# SX1278.net
KiCad netlist of a schematic drawn in Altium Designer
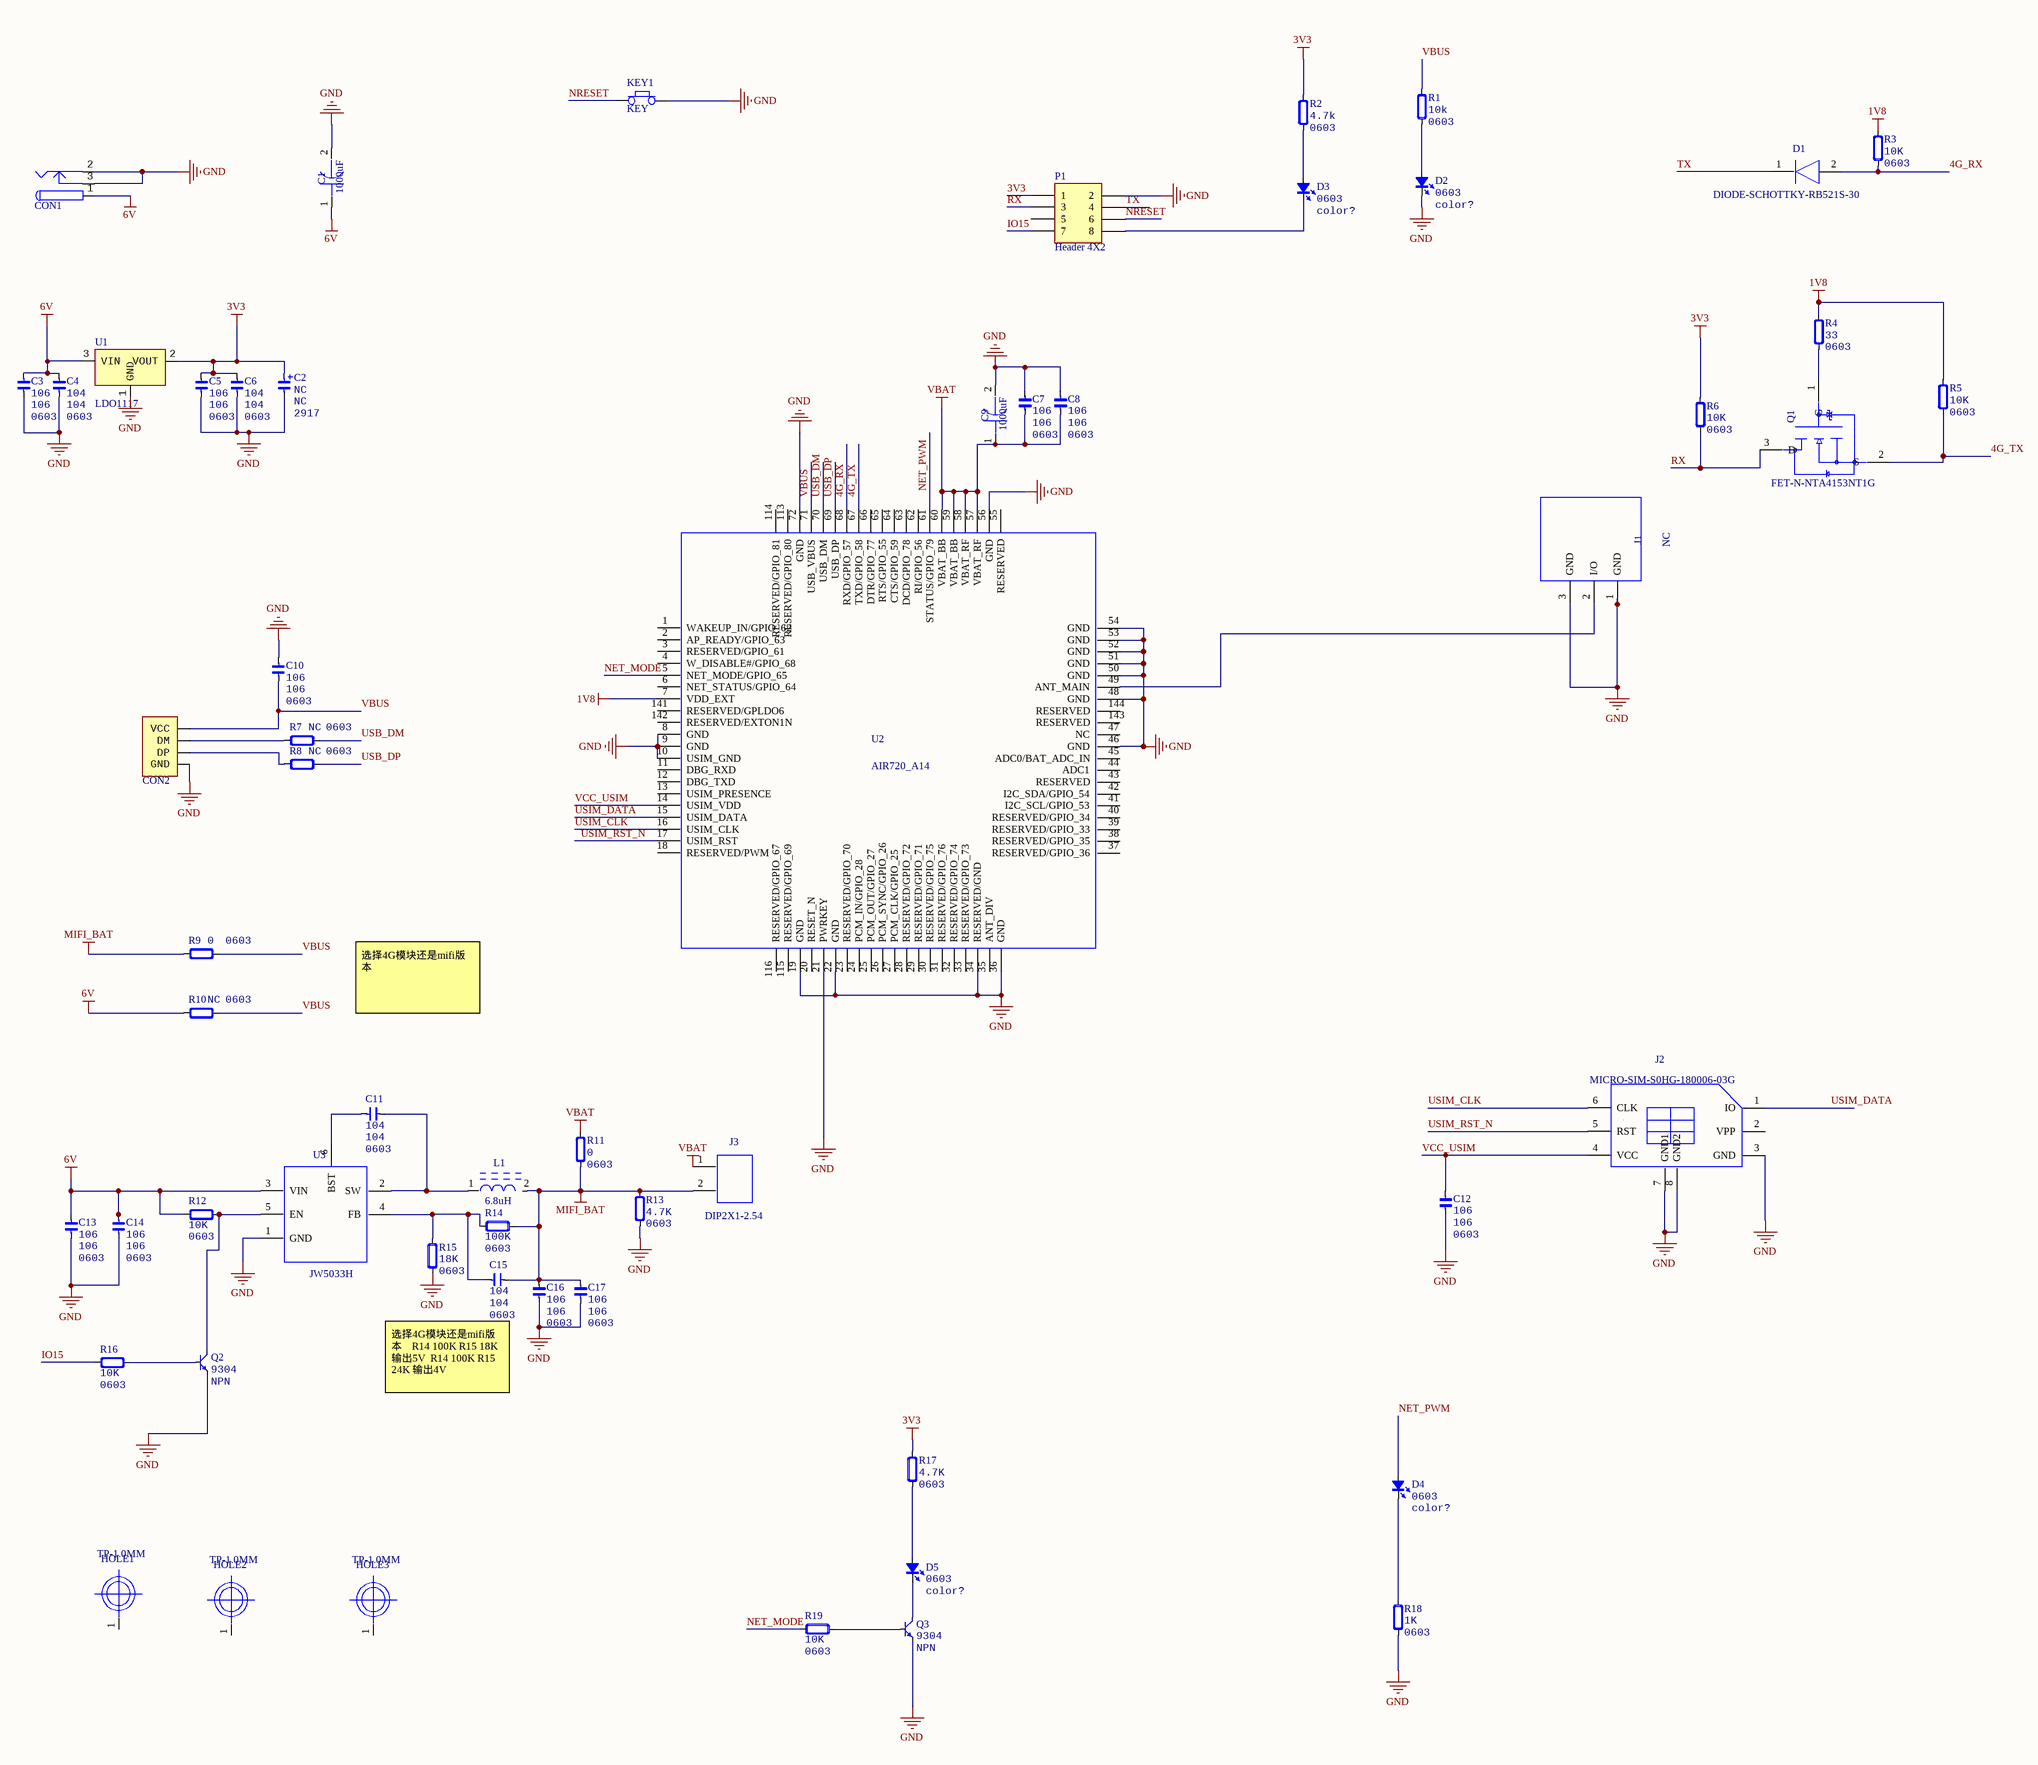
[diagram p0: SX1278.SchDoc]

(export (version "E")
  (design (tool "Eeschema 10.0.6"))
  (components
    (comp (ref "C1")
      (value "1000uF")
      (footprint "CAP-AL-1000UF-10X12")
      (description "贴片电解电容,1000uF/10V")
      (fields (field (name "Comment") "CAP-AL-1000UF-8X10.5"))
      (libsource (lib "4GMODULE") (part "CAP-AL-1000UF-8X10.5"))
    )
    (comp (ref "C2")
      (value "NC")
      (footprint "PCB_PassiveCap:CAP_TAN_D2917")
      (description "Capacitor Tantalum")
      (fields (field (name "ALTIUM_VALUE") "NC") (field (name "TYPE") "2917"))
      (libsource (lib "SCH_Passive") (part "Cap_Tan_2917"))
    )
    (comp (ref "C3")
      (value "106")
      (footprint "PCB_PassiveCap:CAP_0603")
      (description "Capacitor")
      (fields (field (name "ALTIUM_VALUE") "106") (field (name "TYPE") "0603"))
      (libsource (lib "SCH_Passive") (part "Cap_0603"))
    )
    (comp (ref "C4")
      (value "104")
      (footprint "PCB_PassiveCap:CAP_0603")
      (description "Capacitor")
      (fields (field (name "ALTIUM_VALUE") "104") (field (name "TYPE") "0603"))
      (libsource (lib "SCH_Passive") (part "Cap_0603"))
    )
    (comp (ref "C5")
      (value "106")
      (footprint "PCB_PassiveCap:CAP_0603")
      (description "Capacitor")
      (fields (field (name "ALTIUM_VALUE") "106") (field (name "TYPE") "0603"))
      (libsource (lib "SCH_Passive") (part "Cap_0603"))
    )
    (comp (ref "C6")
      (value "104")
      (footprint "PCB_PassiveCap:CAP_0603")
      (description "Capacitor")
      (fields (field (name "ALTIUM_VALUE") "104") (field (name "TYPE") "0603"))
      (libsource (lib "SCH_Passive") (part "Cap_0603"))
    )
    (comp (ref "C7")
      (value "106")
      (footprint "PCB_PassiveCap:CAP_0603")
      (description "Capacitor")
      (fields (field (name "ALTIUM_VALUE") "106") (field (name "TYPE") "0603"))
      (libsource (lib "SCH_Passive") (part "Cap_0603"))
    )
    (comp (ref "C8")
      (value "106")
      (footprint "PCB_PassiveCap:CAP_0603")
      (description "Capacitor")
      (fields (field (name "ALTIUM_VALUE") "106") (field (name "TYPE") "0603"))
      (libsource (lib "SCH_Passive") (part "Cap_0603"))
    )
    (comp (ref "C9")
      (value "1000uF")
      (footprint "CAP-AL-1000UF-10X12")
      (description "贴片电解电容,1000uF/10V")
      (fields (field (name "Comment") "CAP-AL-1000UF-8X10.5"))
      (libsource (lib "4GMODULE") (part "CAP-AL-1000UF-8X10.5"))
    )
    (comp (ref "C10")
      (value "106")
      (footprint "PCB_PassiveCap:CAP_0603")
      (description "Capacitor")
      (fields (field (name "ALTIUM_VALUE") "106") (field (name "TYPE") "0603"))
      (libsource (lib "") (part "Cap_0603_3"))
    )
    (comp (ref "C11")
      (value "104")
      (footprint "PCB_PassiveCap:CAP_0603")
      (description "Capacitor")
      (fields (field (name "ALTIUM_VALUE") "104") (field (name "TYPE") "0603"))
      (libsource (lib "") (part "Cap_0603_2"))
    )
    (comp (ref "C12")
      (value "106")
      (footprint "PCB_PassiveCap:CAP_0603")
      (description "Capacitor")
      (fields (field (name "ALTIUM_VALUE") "106") (field (name "TYPE") "0603"))
      (libsource (lib "SCH_Passive") (part "Cap_0603"))
    )
    (comp (ref "C13")
      (value "106")
      (footprint "PCB_PassiveCap:CAP_0603")
      (description "Capacitor")
      (fields (field (name "ALTIUM_VALUE") "106") (field (name "TYPE") "0603"))
      (libsource (lib "SCH_Passive") (part "Cap_0603"))
    )
    (comp (ref "C14")
      (value "106")
      (footprint "PCB_PassiveCap:CAP_0603")
      (description "Capacitor")
      (fields (field (name "ALTIUM_VALUE") "106") (field (name "TYPE") "0603"))
      (libsource (lib "SCH_Passive") (part "Cap_0603"))
    )
    (comp (ref "C15")
      (value "104")
      (footprint "PCB_PassiveCap:CAP_0603")
      (description "Capacitor")
      (fields (field (name "ALTIUM_VALUE") "104") (field (name "TYPE") "0603"))
      (libsource (lib "") (part "Cap_0603_1"))
    )
    (comp (ref "C16")
      (value "106")
      (footprint "PCB_PassiveCap:CAP_0603")
      (description "Capacitor")
      (fields (field (name "ALTIUM_VALUE") "106") (field (name "TYPE") "0603"))
      (libsource (lib "SCH_Passive") (part "Cap_0603"))
    )
    (comp (ref "C17")
      (value "106")
      (footprint "PCB_PassiveCap:CAP_0603")
      (description "Capacitor")
      (fields (field (name "ALTIUM_VALUE") "106") (field (name "TYPE") "0603"))
      (libsource (lib "SCH_Passive") (part "Cap_0603"))
    )
    (comp (ref "CON1")
      (value "PowerJack_2.5")
      (footprint "DC003A")
      (description "DC Power Jack")
      (libsource (lib "SCH_Connector") (part "PowerJack_2.5"))
    )
    (comp (ref "CON2")
      (value "USB_TypeA")
      (footprint "PCB_USB:USB_TypeA")
      (description "USB")
      (libsource (lib "SCH_USB") (part "USB_TypeA"))
    )
    (comp (ref "D1")
      (value "DIODE-SCHOTTKY-RB521S-30")
      (footprint "SOD523(RB521S)")
      (description "Schottky Diode;30V;200mA/0.6V;SOD-523;0.7mm;ROHS")
      (libsource (lib "4GMODULE") (part "DIODE-SCHOTTKY-RB521S-30"))
    )
    (comp (ref "D2")
      (value "color?")
      (footprint "PCB_ActiveLED:LED_0603_GREEN")
      (description "LED")
      (fields (field (name "TYPE") "0603"))
      (libsource (lib "SCH_Active") (part "LED_0603"))
    )
    (comp (ref "D3")
      (value "color?")
      (footprint "PCB_ActiveLED:LED_0603_GREEN")
      (description "LED")
      (fields (field (name "TYPE") "0603"))
      (libsource (lib "SCH_Active") (part "LED_0603"))
    )
    (comp (ref "D4")
      (value "color?")
      (footprint "PCB_ActiveLED:LED_0603_GREEN")
      (description "LED")
      (fields (field (name "TYPE") "0603"))
      (libsource (lib "SCH_Active") (part "LED_0603"))
    )
    (comp (ref "D5")
      (value "color?")
      (footprint "PCB_ActiveLED:LED_0603_GREEN")
      (description "LED")
      (fields (field (name "TYPE") "0603"))
      (libsource (lib "SCH_Active") (part "LED_0603"))
    )
    (comp (ref "HOLE1")
      (value "TP-1.0MM")
      (footprint "TP-1MM")
      (description "TP-1mm")
      (libsource (lib "4GMODULE") (part "TP-1.0MM"))
    )
    (comp (ref "HOLE2")
      (value "TP-1.0MM")
      (footprint "TP-1MM")
      (description "TP-1mm")
      (libsource (lib "4GMODULE") (part "TP-1.0MM"))
    )
    (comp (ref "HOLE3")
      (value "TP-1.0MM")
      (footprint "TP-1MM")
      (description "TP-1mm")
      (libsource (lib "4GMODULE") (part "TP-1.0MM"))
    )
    (comp (ref "J1")
      (value "NC")
      (footprint "RF-ANT-HJ")
      (description "RF CONNECTOR;3*3*1.25mm;ROHS")
      (fields (field (name "PART NUMBER") "1120333002051"))
      (libsource (lib "4GMODULE") (part "RF-ANT-SOCKET-U.FL-R-SMT"))
    )
    (comp (ref "J2")
      (value "MICRO-SIM-S0HG-180006-03G")
      (footprint "S0HG-180006-03G")
      (description "1.8H掀盖 Micro SIM卡座;16.3*14.66*1.8mm")
      (libsource (lib "4GMODULE") (part "MICRO-SIM-S0HG-180006-03G"))
    )
    (comp (ref "J3")
      (value "DIP2X1-2.54")
      (footprint "DIP2X1-2.54")
      (libsource (lib "4GMODULE") (part "DIP2X1-2.54"))
    )
    (comp (ref "KEY1") (value "KEY") (footprint "key_4") (libsource (lib "HEXCAL_SCH_LIB") (part "KEY")))
    (comp (ref "L1")
      (value "6.8uH")
      (footprint "LVS505020-4R7M-N")
      (fields (field (name "Comment") "LVS505020-4R7M-N"))
      (libsource (lib "4GMODULE") (part "LVS505020-4R7M-N"))
    )
    (comp (ref "P1")
      (value "Header 4X2")
      (footprint "HDR2X4")
      (description "Header, 4-Pin, Dual row")
      (fields (field (name "PUBLISHER") "Altium Limited"))
      (libsource (lib "Miscellaneous Connectors") (part "Header 4X2"))
    )
    (comp (ref "Q1")
      (value "FET-N-NTA4153NT1G")
      (footprint "SOT23-3")
      (description "MOSFET;N-Ch")
      (libsource (lib "4GMODULE") (part "FET-N-NTA4153NT1G"))
    )
    (comp (ref "Q2")
      (value "9304")
      (footprint "PCB_IntegratedCircuit:SOT23-3")
      (description "Transistor")
      (fields (field (name "TYPE") "NPN"))
      (libsource (lib "SCH_Active") (part "BJT_NPN"))
    )
    (comp (ref "Q3")
      (value "9304")
      (footprint "PCB_IntegratedCircuit:SOT23-3")
      (description "Transistor")
      (fields (field (name "TYPE") "NPN"))
      (libsource (lib "SCH_Active") (part "BJT_NPN"))
    )
    (comp (ref "R1")
      (value "10k")
      (footprint "PCB_PassiveRes:RES_0603")
      (description "Resistor")
      (fields (field (name "TYPE") "0603"))
      (libsource (lib "SCH_Passive") (part "Res_0603"))
    )
    (comp (ref "R2")
      (value "4.7k")
      (footprint "PCB_PassiveRes:RES_0603")
      (description "Resistor")
      (fields (field (name "TYPE") "0603"))
      (libsource (lib "SCH_Passive") (part "Res_0603"))
    )
    (comp (ref "R3")
      (value "10K")
      (footprint "PCB_PassiveRes:RES_0603")
      (description "Resistor")
      (fields (field (name "TYPE") "0603"))
      (libsource (lib "SCH_Passive") (part "Res_0603"))
    )
    (comp (ref "R4")
      (value "33")
      (footprint "PCB_PassiveRes:RES_0603")
      (description "Resistor")
      (fields (field (name "TYPE") "0603"))
      (libsource (lib "SCH_Passive") (part "Res_0603"))
    )
    (comp (ref "R5")
      (value "10K")
      (footprint "PCB_PassiveRes:RES_0603")
      (description "Resistor")
      (fields (field (name "TYPE") "0603"))
      (libsource (lib "SCH_Passive") (part "Res_0603"))
    )
    (comp (ref "R6")
      (value "10K")
      (footprint "PCB_PassiveRes:RES_0603")
      (description "Resistor")
      (fields (field (name "TYPE") "0603"))
      (libsource (lib "SCH_Passive") (part "Res_0603"))
    )
    (comp (ref "R7")
      (value "NC")
      (footprint "PCB_PassiveRes:RES_0603")
      (description "Resistor")
      (fields (field (name "TYPE") "0603"))
      (libsource (lib "SCH_Passive") (part "Res_0603"))
    )
    (comp (ref "R8")
      (value "NC")
      (footprint "PCB_PassiveRes:RES_0603")
      (description "Resistor")
      (fields (field (name "TYPE") "0603"))
      (libsource (lib "SCH_Passive") (part "Res_0603"))
    )
    (comp (ref "R9")
      (value "0")
      (footprint "PCB_PassiveRes:RES_0603")
      (description "Resistor")
      (fields (field (name "TYPE") "0603"))
      (libsource (lib "SCH_Passive") (part "Res_0603"))
    )
    (comp (ref "R10")
      (value "NC")
      (footprint "PCB_PassiveRes:RES_0603")
      (description "Resistor")
      (fields (field (name "TYPE") "0603"))
      (libsource (lib "SCH_Passive") (part "Res_0603"))
    )
    (comp (ref "R11")
      (value "0")
      (footprint "PCB_PassiveRes:RES_0603")
      (description "Resistor")
      (fields (field (name "TYPE") "0603"))
      (libsource (lib "SCH_Passive") (part "Res_0603"))
    )
    (comp (ref "R12")
      (value "10K")
      (footprint "PCB_PassiveRes:RES_0603")
      (description "Resistor")
      (fields (field (name "TYPE") "0603"))
      (libsource (lib "SCH_Passive") (part "Res_0603"))
    )
    (comp (ref "R13")
      (value "4.7K")
      (footprint "PCB_PassiveRes:RES_0603")
      (description "Resistor")
      (fields (field (name "TYPE") "0603"))
      (libsource (lib "SCH_Passive") (part "Res_0603"))
    )
    (comp (ref "R14")
      (value "100K")
      (footprint "PCB_PassiveRes:RES_0603")
      (description "Resistor")
      (fields (field (name "TYPE") "0603"))
      (libsource (lib "SCH_Passive") (part "Res_0603"))
    )
    (comp (ref "R15")
      (value "18K")
      (footprint "PCB_PassiveRes:RES_0603")
      (description "Resistor")
      (fields (field (name "TYPE") "0603"))
      (libsource (lib "SCH_Passive") (part "Res_0603"))
    )
    (comp (ref "R16")
      (value "10K")
      (footprint "PCB_PassiveRes:RES_0603")
      (description "Resistor")
      (fields (field (name "TYPE") "0603"))
      (libsource (lib "SCH_Passive") (part "Res_0603"))
    )
    (comp (ref "R17")
      (value "4.7K")
      (footprint "PCB_PassiveRes:RES_0603")
      (description "Resistor")
      (fields (field (name "TYPE") "0603"))
      (libsource (lib "SCH_Passive") (part "Res_0603"))
    )
    (comp (ref "R18")
      (value "1K")
      (footprint "PCB_PassiveRes:RES_0603")
      (description "Resistor")
      (fields (field (name "TYPE") "0603"))
      (libsource (lib "SCH_Passive") (part "Res_0603"))
    )
    (comp (ref "R19")
      (value "10K")
      (footprint "PCB_PassiveRes:RES_0603")
      (description "Resistor")
      (fields (field (name "TYPE") "0603"))
      (libsource (lib "SCH_Passive") (part "Res_0603"))
    )
    (comp (ref "U1")
      (value "LDO1117")
      (footprint "SOT223-3")
      (description "Power")
      (libsource (lib "SCH_IntegratedCircuit") (part "LDO1117"))
    )
    (comp (ref "U2")
      (value "AIR720_A14")
      (footprint "AIR726-A")
      (libsource (lib "4GMODULE") (part "AIR720_A14"))
    )
    (comp (ref "U3") (value "JW5033H") (footprint "JW5033S") (libsource (lib "4GMODULE") (part "JW5033H")))
  )
  (nets
    (net (code "1") (name "/4G_RX") (class "Default")
      (node (ref "D1") (pin "2") (pintype "passive"))
      (node (ref "R3") (pin "2") (pinfunction "2_2") (pintype "passive"))
      (node (ref "U2") (pin "68") (pinfunction "RXD/GPIO_57_68") (pintype "passive"))
    )
    (net (code "2") (name "/4G_TX") (class "Default")
      (node (ref "Q1") (pin "2") (pinfunction "S_2") (pintype "passive"))
      (node (ref "R5") (pin "2") (pinfunction "2_2") (pintype "passive"))
      (node (ref "U2") (pin "67") (pinfunction "TXD/GPIO_58_67") (pintype "passive"))
    )
    (net (code "3") (name "/IO15") (class "Default")
      (node (ref "P1") (pin "7") (pinfunction "7_7") (pintype "passive"))
      (node (ref "R16") (pin "1") (pinfunction "1_1") (pintype "passive"))
    )
    (net (code "4") (name "/NET_MODE") (class "Default")
      (node (ref "R19") (pin "1") (pinfunction "1_1") (pintype "passive"))
      (node (ref "U2") (pin "5") (pinfunction "NET_MODE/GPIO_65_5") (pintype "passive"))
    )
    (net (code "5") (name "/NET_PWM") (class "Default")
      (node (ref "D4") (pin "1") (pinfunction "A_1") (pintype "passive"))
      (node (ref "U2") (pin "61") (pinfunction "STATUS/GPIO_79_61") (pintype "passive"))
    )
    (net (code "6") (name "/NRESET") (class "Default")
      (node (ref "KEY1") (pin "1") (pinfunction "1_1") (pintype "passive"))
      (node (ref "P1") (pin "6") (pinfunction "6_6") (pintype "passive"))
    )
    (net (code "7") (name "/RX") (class "Default")
      (node (ref "P1") (pin "3") (pinfunction "3_3") (pintype "passive"))
      (node (ref "Q1") (pin "3") (pinfunction "D_3") (pintype "passive"))
      (node (ref "R6") (pin "2") (pinfunction "2_2") (pintype "passive"))
    )
    (net (code "8") (name "/TX") (class "Default")
      (node (ref "D1") (pin "1") (pintype "passive"))
      (node (ref "P1") (pin "4") (pinfunction "4_4") (pintype "passive"))
    )
    (net (code "9") (name "/USB_DM") (class "Default")
      (node (ref "R7") (pin "2") (pinfunction "2_2") (pintype "passive"))
      (node (ref "U2") (pin "70") (pinfunction "USB_DM_70") (pintype "passive"))
    )
    (net (code "10") (name "/USB_DP") (class "Default")
      (node (ref "R8") (pin "2") (pinfunction "2_2") (pintype "passive"))
      (node (ref "U2") (pin "69") (pinfunction "USB_DP_69") (pintype "passive"))
    )
    (net (code "11") (name "/USIM_CLK") (class "Default")
      (node (ref "J2") (pin "6") (pinfunction "CLK_6") (pintype "passive"))
      (node (ref "U2") (pin "16") (pinfunction "USIM_CLK_16") (pintype "passive"))
    )
    (net (code "12") (name "/USIM_DATA") (class "Default")
      (node (ref "J2") (pin "1") (pinfunction "IO_1") (pintype "passive"))
      (node (ref "U2") (pin "15") (pinfunction "USIM_DATA_15") (pintype "passive"))
    )
    (net (code "13") (name "/USIM_RST_N") (class "Default")
      (node (ref "J2") (pin "5") (pinfunction "RST_5") (pintype "passive"))
      (node (ref "U2") (pin "17") (pinfunction "USIM_RST_17") (pintype "passive"))
    )
    (net (code "14") (name "/VBUS") (class "Default")
      (node (ref "C10") (pin "2") (pinfunction "2_2") (pintype "passive"))
      (node (ref "CON2") (pin "1") (pinfunction "VCC_1") (pintype "passive"))
      (node (ref "R1") (pin "1") (pinfunction "1_1") (pintype "passive"))
      (node (ref "R10") (pin "2") (pinfunction "2_2") (pintype "passive"))
      (node (ref "R9") (pin "2") (pinfunction "2_2") (pintype "passive"))
      (node (ref "U2") (pin "71") (pinfunction "USB_VBUS_71") (pintype "passive"))
    )
    (net (code "15") (name "/VCC_USIM") (class "Default")
      (node (ref "C12") (pin "2") (pinfunction "2_2") (pintype "passive"))
      (node (ref "J2") (pin "4") (pinfunction "VCC_4") (pintype "passive"))
      (node (ref "U2") (pin "14") (pinfunction "USIM_VDD_14") (pintype "passive"))
    )
    (net (code "16") (name "1V8") (class "Default")
      (node (ref "R3") (pin "1") (pinfunction "1_1") (pintype "passive"))
      (node (ref "R4") (pin "1") (pinfunction "1_1") (pintype "passive"))
      (node (ref "R5") (pin "1") (pinfunction "1_1") (pintype "passive"))
      (node (ref "U2") (pin "7") (pinfunction "VDD_EXT_7") (pintype "passive"))
    )
    (net (code "17") (name "3V3") (class "Default")
      (node (ref "C2") (pin "1") (pinfunction "1_1") (pintype "passive"))
      (node (ref "C5") (pin "2") (pinfunction "2_2") (pintype "passive"))
      (node (ref "C6") (pin "2") (pinfunction "2_2") (pintype "passive"))
      (node (ref "P1") (pin "1") (pinfunction "1_1") (pintype "passive"))
      (node (ref "R17") (pin "2") (pinfunction "2_2") (pintype "passive"))
      (node (ref "R2") (pin "1") (pinfunction "1_1") (pintype "passive"))
      (node (ref "R6") (pin "1") (pinfunction "1_1") (pintype "passive"))
      (node (ref "U1") (pin "2") (pinfunction "VOUT_2") (pintype "passive"))
    )
    (net (code "18") (name "6V") (class "Default")
      (node (ref "C1") (pin "1") (pintype "passive"))
      (node (ref "C13") (pin "2") (pinfunction "2_2") (pintype "passive"))
      (node (ref "C14") (pin "2") (pinfunction "2_2") (pintype "passive"))
      (node (ref "C3") (pin "2") (pinfunction "2_2") (pintype "passive"))
      (node (ref "C4") (pin "2") (pinfunction "2_2") (pintype "passive"))
      (node (ref "CON1") (pin "1") (pinfunction "1_1") (pintype "power_in"))
      (node (ref "R10") (pin "1") (pinfunction "1_1") (pintype "passive"))
      (node (ref "R12") (pin "1") (pinfunction "1_1") (pintype "passive"))
      (node (ref "U1") (pin "3") (pinfunction "VIN_3") (pintype "passive"))
      (node (ref "U3") (pin "3") (pinfunction "VIN_3") (pintype "passive"))
    )
    (net (code "19") (name "GND") (class "Default")
      (node (ref "C1") (pin "2") (pintype "passive"))
      (node (ref "C10") (pin "1") (pinfunction "1_1") (pintype "passive"))
      (node (ref "C12") (pin "1") (pinfunction "1_1") (pintype "passive"))
      (node (ref "C13") (pin "1") (pinfunction "1_1") (pintype "passive"))
      (node (ref "C14") (pin "1") (pinfunction "1_1") (pintype "passive"))
      (node (ref "C16") (pin "1") (pinfunction "1_1") (pintype "passive"))
      (node (ref "C17") (pin "1") (pinfunction "1_1") (pintype "passive"))
      (node (ref "C2") (pin "2") (pinfunction "2_2") (pintype "passive"))
      (node (ref "C3") (pin "1") (pinfunction "1_1") (pintype "passive"))
      (node (ref "C4") (pin "1") (pinfunction "1_1") (pintype "passive"))
      (node (ref "C5") (pin "1") (pinfunction "1_1") (pintype "passive"))
      (node (ref "C6") (pin "1") (pinfunction "1_1") (pintype "passive"))
      (node (ref "C7") (pin "2") (pinfunction "2_2") (pintype "passive"))
      (node (ref "C8") (pin "2") (pinfunction "2_2") (pintype "passive"))
      (node (ref "C9") (pin "2") (pintype "passive"))
      (node (ref "CON1") (pin "2") (pinfunction "2_2") (pintype "power_in"))
      (node (ref "CON1") (pin "3") (pinfunction "3_3") (pintype "power_in"))
      (node (ref "CON2") (pin "4") (pinfunction "GND_4") (pintype "passive"))
      (node (ref "D2") (pin "2") (pinfunction "K_2") (pintype "passive"))
      (node (ref "J1") (pin "1") (pinfunction "GND_1") (pintype "passive"))
      (node (ref "J1") (pin "3") (pinfunction "GND_3") (pintype "passive"))
      (node (ref "J2") (pin "3") (pinfunction "GND_3") (pintype "passive"))
      (node (ref "J2") (pin "7") (pinfunction "GND1_7") (pintype "passive"))
      (node (ref "J2") (pin "8") (pinfunction "GND2_8") (pintype "passive"))
      (node (ref "KEY1") (pin "2") (pinfunction "2_2") (pintype "passive"))
      (node (ref "P1") (pin "2") (pinfunction "2_2") (pintype "passive"))
      (node (ref "Q2") (pin "2") (pinfunction "E_2") (pintype "passive"))
      (node (ref "Q3") (pin "2") (pinfunction "E_2") (pintype "passive"))
      (node (ref "R13") (pin "1") (pinfunction "1_1") (pintype "passive"))
      (node (ref "R15") (pin "1") (pinfunction "1_1") (pintype "passive"))
      (node (ref "R18") (pin "1") (pinfunction "1_1") (pintype "passive"))
      (node (ref "U1") (pin "1") (pinfunction "GND_1") (pintype "passive"))
      (node (ref "U2") (pin "10") (pinfunction "USIM_GND_10") (pintype "passive"))
      (node (ref "U2") (pin "100") (pinfunction "GND_100") (pintype "power_in"))
      (node (ref "U2") (pin "101") (pinfunction "GND_101") (pintype "power_in"))
      (node (ref "U2") (pin "102") (pinfunction "GND_102") (pintype "power_in"))
      (node (ref "U2") (pin "103") (pinfunction "GND_103") (pintype "power_in"))
      (node (ref "U2") (pin "104") (pinfunction "GND_104") (pintype "power_in"))
      (node (ref "U2") (pin "105") (pinfunction "GND_105") (pintype "power_in"))
      (node (ref "U2") (pin "106") (pinfunction "GND_106") (pintype "power_in"))
      (node (ref "U2") (pin "107") (pinfunction "GND_107") (pintype "power_in"))
      (node (ref "U2") (pin "108") (pinfunction "GND_108") (pintype "power_in"))
      (node (ref "U2") (pin "109") (pinfunction "GND_109") (pintype "power_in"))
      (node (ref "U2") (pin "110") (pinfunction "GND_110") (pintype "power_in"))
      (node (ref "U2") (pin "111") (pinfunction "GND_111") (pintype "power_in"))
      (node (ref "U2") (pin "112") (pinfunction "GND_112") (pintype "power_in"))
      (node (ref "U2") (pin "19") (pinfunction "GND_19") (pintype "passive"))
      (node (ref "U2") (pin "21") (pinfunction "PWRKEY_21") (pintype "passive"))
      (node (ref "U2") (pin "22") (pinfunction "GND_22") (pintype "passive"))
      (node (ref "U2") (pin "34") (pinfunction "RESERVED/GND_34") (pintype "passive"))
      (node (ref "U2") (pin "36") (pinfunction "GND_36") (pintype "passive"))
      (node (ref "U2") (pin "46") (pinfunction "GND_46") (pintype "passive"))
      (node (ref "U2") (pin "48") (pinfunction "GND_48") (pintype "passive"))
      (node (ref "U2") (pin "50") (pinfunction "GND_50") (pintype "passive"))
      (node (ref "U2") (pin "51") (pinfunction "GND_51") (pintype "passive"))
      (node (ref "U2") (pin "52") (pinfunction "GND_52") (pintype "passive"))
      (node (ref "U2") (pin "53") (pinfunction "GND_53") (pintype "passive"))
      (node (ref "U2") (pin "54") (pinfunction "GND_54") (pintype "passive"))
      (node (ref "U2") (pin "56") (pinfunction "GND_56") (pintype "passive"))
      (node (ref "U2") (pin "72") (pinfunction "GND_72") (pintype "passive"))
      (node (ref "U2") (pin "8") (pinfunction "GND_8") (pintype "passive"))
      (node (ref "U2") (pin "85") (pinfunction "GND_85") (pintype "power_in"))
      (node (ref "U2") (pin "86") (pinfunction "GND_86") (pintype "power_in"))
      (node (ref "U2") (pin "87") (pinfunction "GND_87") (pintype "power_in"))
      (node (ref "U2") (pin "88") (pinfunction "GND_88") (pintype "power_in"))
      (node (ref "U2") (pin "89") (pinfunction "GND_89") (pintype "power_in"))
      (node (ref "U2") (pin "9") (pinfunction "GND_9") (pintype "passive"))
      (node (ref "U2") (pin "90") (pinfunction "GND_90") (pintype "power_in"))
      (node (ref "U2") (pin "91") (pinfunction "GND_91") (pintype "power_in"))
      (node (ref "U2") (pin "92") (pinfunction "GND_92") (pintype "power_in"))
      (node (ref "U2") (pin "93") (pinfunction "GND_93") (pintype "power_in"))
      (node (ref "U2") (pin "94") (pinfunction "GND_94") (pintype "power_in"))
      (node (ref "U2") (pin "95") (pinfunction "GND_95") (pintype "power_in"))
      (node (ref "U2") (pin "96") (pinfunction "GND_96") (pintype "power_in"))
      (node (ref "U2") (pin "97") (pinfunction "GND_97") (pintype "power_in"))
      (node (ref "U2") (pin "98") (pinfunction "GND_98") (pintype "power_in"))
      (node (ref "U2") (pin "99") (pinfunction "GND_99") (pintype "power_in"))
      (node (ref "U3") (pin "1") (pinfunction "GND_1") (pintype "passive"))
    )
    (net (code "20") (name "MIFI_BAT") (class "Default")
      (node (ref "C15") (pin "2") (pinfunction "2_2") (pintype "passive"))
      (node (ref "C16") (pin "2") (pinfunction "2_2") (pintype "passive"))
      (node (ref "C17") (pin "2") (pinfunction "2_2") (pintype "passive"))
      (node (ref "J3") (pin "2") (pintype "passive"))
      (node (ref "L1") (pin "2") (pintype "passive"))
      (node (ref "R11") (pin "1") (pinfunction "1_1") (pintype "passive"))
      (node (ref "R13") (pin "2") (pinfunction "2_2") (pintype "passive"))
      (node (ref "R14") (pin "2") (pinfunction "2_2") (pintype "passive"))
      (node (ref "R9") (pin "1") (pinfunction "1_1") (pintype "passive"))
    )
    (net (code "21") (name "Net-(CON2-DM)") (class "Default")
      (node (ref "CON2") (pin "2") (pinfunction "DM_2") (pintype "passive"))
      (node (ref "R7") (pin "1") (pinfunction "1_1") (pintype "passive"))
    )
    (net (code "22") (name "Net-(CON2-DP)") (class "Default")
      (node (ref "CON2") (pin "3") (pinfunction "DP_3") (pintype "passive"))
      (node (ref "R8") (pin "1") (pinfunction "1_1") (pintype "passive"))
    )
    (net (code "23") (name "Net-(D2-A)") (class "Default")
      (node (ref "D2") (pin "1") (pinfunction "A_1") (pintype "passive"))
      (node (ref "R1") (pin "2") (pinfunction "2_2") (pintype "passive"))
    )
    (net (code "24") (name "Net-(D3-A)") (class "Default")
      (node (ref "D3") (pin "1") (pinfunction "A_1") (pintype "passive"))
      (node (ref "R2") (pin "2") (pinfunction "2_2") (pintype "passive"))
    )
    (net (code "25") (name "Net-(D3-K)") (class "Default")
      (node (ref "D3") (pin "2") (pinfunction "K_2") (pintype "passive"))
      (node (ref "P1") (pin "8") (pinfunction "8_8") (pintype "passive"))
    )
    (net (code "26") (name "Net-(D4-K)") (class "Default")
      (node (ref "D4") (pin "2") (pinfunction "K_2") (pintype "passive"))
      (node (ref "R18") (pin "2") (pinfunction "2_2") (pintype "passive"))
    )
    (net (code "27") (name "Net-(D5-A)") (class "Default")
      (node (ref "D5") (pin "1") (pinfunction "A_1") (pintype "passive"))
      (node (ref "R17") (pin "1") (pinfunction "1_1") (pintype "passive"))
    )
    (net (code "28") (name "Net-(D5-K)") (class "Default")
      (node (ref "D5") (pin "2") (pinfunction "K_2") (pintype "passive"))
      (node (ref "Q3") (pin "3") (pinfunction "C_3") (pintype "passive"))
    )
    (net (code "29") (name "Net-(J1-I{slash}O)") (class "Default")
      (node (ref "J1") (pin "2") (pinfunction "I/O_2") (pintype "passive"))
      (node (ref "U2") (pin "49") (pinfunction "ANT_MAIN_49") (pintype "passive"))
    )
    (net (code "30") (name "Net-(Q1-G)") (class "Default")
      (node (ref "Q1") (pin "1") (pinfunction "G_1") (pintype "passive"))
      (node (ref "R4") (pin "2") (pinfunction "2_2") (pintype "passive"))
    )
    (net (code "31") (name "Net-(Q2-B)") (class "Default")
      (node (ref "Q2") (pin "1") (pinfunction "B_1") (pintype "passive"))
      (node (ref "R16") (pin "2") (pinfunction "2_2") (pintype "passive"))
    )
    (net (code "32") (name "Net-(Q2-C)") (class "Default")
      (node (ref "Q2") (pin "3") (pinfunction "C_3") (pintype "passive"))
      (node (ref "R12") (pin "2") (pinfunction "2_2") (pintype "passive"))
      (node (ref "U3") (pin "5") (pinfunction "EN_5") (pintype "passive"))
    )
    (net (code "33") (name "Net-(Q3-B)") (class "Default")
      (node (ref "Q3") (pin "1") (pinfunction "B_1") (pintype "passive"))
      (node (ref "R19") (pin "2") (pinfunction "2_2") (pintype "passive"))
    )
    (net (code "34") (name "Net-(U3-BST)") (class "Default")
      (node (ref "C11") (pin "2") (pinfunction "2_2") (pintype "passive"))
      (node (ref "U3") (pin "6") (pinfunction "BST_6") (pintype "passive"))
    )
    (net (code "35") (name "Net-(U3-FB)") (class "Default")
      (node (ref "C15") (pin "1") (pinfunction "1_1") (pintype "passive"))
      (node (ref "R14") (pin "1") (pinfunction "1_1") (pintype "passive"))
      (node (ref "R15") (pin "2") (pinfunction "2_2") (pintype "passive"))
      (node (ref "U3") (pin "4") (pinfunction "FB_4") (pintype "passive"))
    )
    (net (code "36") (name "Net-(U3-SW)") (class "Default")
      (node (ref "C11") (pin "1") (pinfunction "1_1") (pintype "passive"))
      (node (ref "L1") (pin "1") (pintype "passive"))
      (node (ref "U3") (pin "2") (pinfunction "SW_2") (pintype "passive"))
    )
    (net (code "37") (name "VBAT") (class "Default")
      (node (ref "C7") (pin "1") (pinfunction "1_1") (pintype "passive"))
      (node (ref "C8") (pin "1") (pinfunction "1_1") (pintype "passive"))
      (node (ref "C9") (pin "1") (pintype "passive"))
      (node (ref "J3") (pin "1") (pintype "passive"))
      (node (ref "R11") (pin "2") (pinfunction "2_2") (pintype "passive"))
      (node (ref "U2") (pin "57") (pinfunction "VBAT_RF_57") (pintype "passive"))
      (node (ref "U2") (pin "58") (pinfunction "VBAT_RF_58") (pintype "passive"))
      (node (ref "U2") (pin "59") (pinfunction "VBAT_BB_59") (pintype "passive"))
      (node (ref "U2") (pin "60") (pinfunction "VBAT_BB_60") (pintype "passive"))
    )
    (net (code "38") (name "unconnected-(HOLE1-Pad1)") (class "Default")
      (node (ref "HOLE1") (pin "1") (pintype "passive"))
    )
    (net (code "39") (name "unconnected-(HOLE2-Pad1)") (class "Default")
      (node (ref "HOLE2") (pin "1") (pintype "passive"))
    )
    (net (code "40") (name "unconnected-(HOLE3-Pad1)") (class "Default")
      (node (ref "HOLE3") (pin "1") (pintype "passive"))
    )
    (net (code "41") (name "unconnected-(J2-VPP-Pad2)") (class "Default")
      (node (ref "J2") (pin "2") (pinfunction "VPP_2") (pintype "passive"))
    )
    (net (code "42") (name "unconnected-(P1-Pad5)") (class "Default")
      (node (ref "P1") (pin "5") (pinfunction "5_5") (pintype "passive"))
    )
    (net (code "43") (name "unconnected-(U2-ADC0{slash}BAT_ADC_IN-Pad45)") (class "Default")
      (node (ref "U2") (pin "45") (pinfunction "ADC0/BAT_ADC_IN_45") (pintype "passive"))
    )
    (net (code "44") (name "unconnected-(U2-ADC1-Pad44)") (class "Default")
      (node (ref "U2") (pin "44") (pinfunction "ADC1_44") (pintype "passive"))
    )
    (net (code "45") (name "unconnected-(U2-ANT_DIV-Pad35)") (class "Default")
      (node (ref "U2") (pin "35") (pinfunction "ANT_DIV_35") (pintype "passive"))
    )
    (net (code "46") (name "unconnected-(U2-AP_READY{slash}GPIO_63-Pad2)") (class "Default")
      (node (ref "U2") (pin "2") (pinfunction "AP_READY/GPIO_63_2") (pintype "passive"))
    )
    (net (code "47") (name "unconnected-(U2-CTS{slash}GPIO_59-Pad64)") (class "Default")
      (node (ref "U2") (pin "64") (pinfunction "CTS/GPIO_59_64") (pintype "passive"))
    )
    (net (code "48") (name "unconnected-(U2-DBG_RXD-Pad11)") (class "Default")
      (node (ref "U2") (pin "11") (pinfunction "DBG_RXD_11") (pintype "passive"))
    )
    (net (code "49") (name "unconnected-(U2-DBG_TXD-Pad12)") (class "Default")
      (node (ref "U2") (pin "12") (pinfunction "DBG_TXD_12") (pintype "passive"))
    )
    (net (code "50") (name "unconnected-(U2-DCD{slash}GPIO_78-Pad63)") (class "Default")
      (node (ref "U2") (pin "63") (pinfunction "DCD/GPIO_78_63") (pintype "passive"))
    )
    (net (code "51") (name "unconnected-(U2-DTR{slash}GPIO_77-Pad66)") (class "Default")
      (node (ref "U2") (pin "66") (pinfunction "DTR/GPIO_77_66") (pintype "passive"))
    )
    (net (code "52") (name "unconnected-(U2-I2C_SCL{slash}GPIO_53-Pad41)") (class "Default")
      (node (ref "U2") (pin "41") (pinfunction "I2C_SCL/GPIO_53_41") (pintype "passive"))
    )
    (net (code "53") (name "unconnected-(U2-I2C_SDA{slash}GPIO_54-Pad42)") (class "Default")
      (node (ref "U2") (pin "42") (pinfunction "I2C_SDA/GPIO_54_42") (pintype "passive"))
    )
    (net (code "54") (name "unconnected-(U2-NC-Pad47)") (class "Default")
      (node (ref "U2") (pin "47") (pinfunction "NC_47") (pintype "passive"))
    )
    (net (code "55") (name "unconnected-(U2-NET_STATUS{slash}GPIO_64-Pad6)") (class "Default")
      (node (ref "U2") (pin "6") (pinfunction "NET_STATUS/GPIO_64_6") (pintype "passive"))
    )
    (net (code "56") (name "unconnected-(U2-PCM_CLK{slash}GPIO_25-Pad27)") (class "Default")
      (node (ref "U2") (pin "27") (pinfunction "PCM_CLK/GPIO_25_27") (pintype "passive"))
    )
    (net (code "57") (name "unconnected-(U2-PCM_IN{slash}GPIO_28-Pad24)") (class "Default")
      (node (ref "U2") (pin "24") (pinfunction "PCM_IN/GPIO_28_24") (pintype "passive"))
    )
    (net (code "58") (name "unconnected-(U2-PCM_OUT{slash}GPIO_27-Pad25)") (class "Default")
      (node (ref "U2") (pin "25") (pinfunction "PCM_OUT/GPIO_27_25") (pintype "passive"))
    )
    (net (code "59") (name "unconnected-(U2-PCM_SYNC{slash}GPIO_26-Pad26)") (class "Default")
      (node (ref "U2") (pin "26") (pinfunction "PCM_SYNC/GPIO_26_26") (pintype "passive"))
    )
    (net (code "60") (name "unconnected-(U2-RESERVED-Pad43)") (class "Default")
      (node (ref "U2") (pin "43") (pinfunction "RESERVED_43") (pintype "passive"))
    )
    (net (code "61") (name "unconnected-(U2-RESERVED-Pad55)") (class "Default")
      (node (ref "U2") (pin "55") (pinfunction "RESERVED_55") (pintype "passive"))
    )
    (net (code "62") (name "unconnected-(U2-RESERVED-Pad143)") (class "Default")
      (node (ref "U2") (pin "143") (pinfunction "RESERVED_143") (pintype "passive"))
    )
    (net (code "63") (name "unconnected-(U2-RESERVED-Pad144)") (class "Default")
      (node (ref "U2") (pin "144") (pinfunction "RESERVED_144") (pintype "passive"))
    )
    (net (code "64") (name "unconnected-(U2-RESERVED{slash}EXTON1N-Pad142)") (class "Default")
      (node (ref "U2") (pin "142") (pinfunction "RESERVED/EXTON1N_142") (pintype "passive"))
    )
    (net (code "65") (name "unconnected-(U2-RESERVED{slash}GPIO_33-Pad39)") (class "Default")
      (node (ref "U2") (pin "39") (pinfunction "RESERVED/GPIO_33_39") (pintype "passive"))
    )
    (net (code "66") (name "unconnected-(U2-RESERVED{slash}GPIO_34-Pad40)") (class "Default")
      (node (ref "U2") (pin "40") (pinfunction "RESERVED/GPIO_34_40") (pintype "passive"))
    )
    (net (code "67") (name "unconnected-(U2-RESERVED{slash}GPIO_35-Pad38)") (class "Default")
      (node (ref "U2") (pin "38") (pinfunction "RESERVED/GPIO_35_38") (pintype "passive"))
    )
    (net (code "68") (name "unconnected-(U2-RESERVED{slash}GPIO_36-Pad37)") (class "Default")
      (node (ref "U2") (pin "37") (pinfunction "RESERVED/GPIO_36_37") (pintype "passive"))
    )
    (net (code "69") (name "unconnected-(U2-RESERVED{slash}GPIO_61-Pad3)") (class "Default")
      (node (ref "U2") (pin "3") (pinfunction "RESERVED/GPIO_61_3") (pintype "passive"))
    )
    (net (code "70") (name "unconnected-(U2-RESERVED{slash}GPIO_67-Pad116)") (class "Default")
      (node (ref "U2") (pin "116") (pinfunction "RESERVED/GPIO_67_116") (pintype "passive"))
    )
    (net (code "71") (name "unconnected-(U2-RESERVED{slash}GPIO_69-Pad115)") (class "Default")
      (node (ref "U2") (pin "115") (pinfunction "RESERVED/GPIO_69_115") (pintype "passive"))
    )
    (net (code "72") (name "unconnected-(U2-RESERVED{slash}GPIO_70-Pad23)") (class "Default")
      (node (ref "U2") (pin "23") (pinfunction "RESERVED/GPIO_70_23") (pintype "passive"))
    )
    (net (code "73") (name "unconnected-(U2-RESERVED{slash}GPIO_71-Pad29)") (class "Default")
      (node (ref "U2") (pin "29") (pinfunction "RESERVED/GPIO_71_29") (pintype "passive"))
    )
    (net (code "74") (name "unconnected-(U2-RESERVED{slash}GPIO_72-Pad28)") (class "Default")
      (node (ref "U2") (pin "28") (pinfunction "RESERVED/GPIO_72_28") (pintype "passive"))
    )
    (net (code "75") (name "unconnected-(U2-RESERVED{slash}GPIO_73-Pad33)") (class "Default")
      (node (ref "U2") (pin "33") (pinfunction "RESERVED/GPIO_73_33") (pintype "passive"))
    )
    (net (code "76") (name "unconnected-(U2-RESERVED{slash}GPIO_74-Pad32)") (class "Default")
      (node (ref "U2") (pin "32") (pinfunction "RESERVED/GPIO_74_32") (pintype "passive"))
    )
    (net (code "77") (name "unconnected-(U2-RESERVED{slash}GPIO_75-Pad30)") (class "Default")
      (node (ref "U2") (pin "30") (pinfunction "RESERVED/GPIO_75_30") (pintype "passive"))
    )
    (net (code "78") (name "unconnected-(U2-RESERVED{slash}GPIO_76-Pad31)") (class "Default")
      (node (ref "U2") (pin "31") (pinfunction "RESERVED/GPIO_76_31") (pintype "passive"))
    )
    (net (code "79") (name "unconnected-(U2-RESERVED{slash}GPIO_80-Pad113)") (class "Default")
      (node (ref "U2") (pin "113") (pinfunction "RESERVED/GPIO_80_113") (pintype "passive"))
    )
    (net (code "80") (name "unconnected-(U2-RESERVED{slash}GPIO_81-Pad114)") (class "Default")
      (node (ref "U2") (pin "114") (pinfunction "RESERVED/GPIO_81_114") (pintype "passive"))
    )
    (net (code "81") (name "unconnected-(U2-RESERVED{slash}GPLDO6-Pad141)") (class "Default")
      (node (ref "U2") (pin "141") (pinfunction "RESERVED/GPLDO6_141") (pintype "passive"))
    )
    (net (code "82") (name "unconnected-(U2-RESERVED{slash}PWM-Pad18)") (class "Default")
      (node (ref "U2") (pin "18") (pinfunction "RESERVED/PWM_18") (pintype "passive"))
    )
    (net (code "83") (name "unconnected-(U2-RESET_N-Pad20)") (class "Default")
      (node (ref "U2") (pin "20") (pinfunction "RESET_N_20") (pintype "passive"))
    )
    (net (code "84") (name "unconnected-(U2-RI{slash}GPIO_56-Pad62)") (class "Default")
      (node (ref "U2") (pin "62") (pinfunction "RI/GPIO_56_62") (pintype "passive"))
    )
    (net (code "85") (name "unconnected-(U2-RTS{slash}GPIO_55-Pad65)") (class "Default")
      (node (ref "U2") (pin "65") (pinfunction "RTS/GPIO_55_65") (pintype "passive"))
    )
    (net (code "86") (name "unconnected-(U2-USIM_PRESENCE-Pad13)") (class "Default")
      (node (ref "U2") (pin "13") (pinfunction "USIM_PRESENCE_13") (pintype "passive"))
    )
    (net (code "87") (name "unconnected-(U2-WAKEUP_IN{slash}GPIO_62-Pad1)") (class "Default")
      (node (ref "U2") (pin "1") (pinfunction "WAKEUP_IN/GPIO_62_1") (pintype "passive"))
    )
    (net (code "88") (name "unconnected-(U2-W_DISABLE#{slash}GPIO_68-Pad4)") (class "Default")
      (node (ref "U2") (pin "4") (pinfunction "W_DISABLE#/GPIO_68_4") (pintype "passive"))
    )
  )
)
